# peripheral.net
KiCad netlist of a schematic drawn in Altium Designer
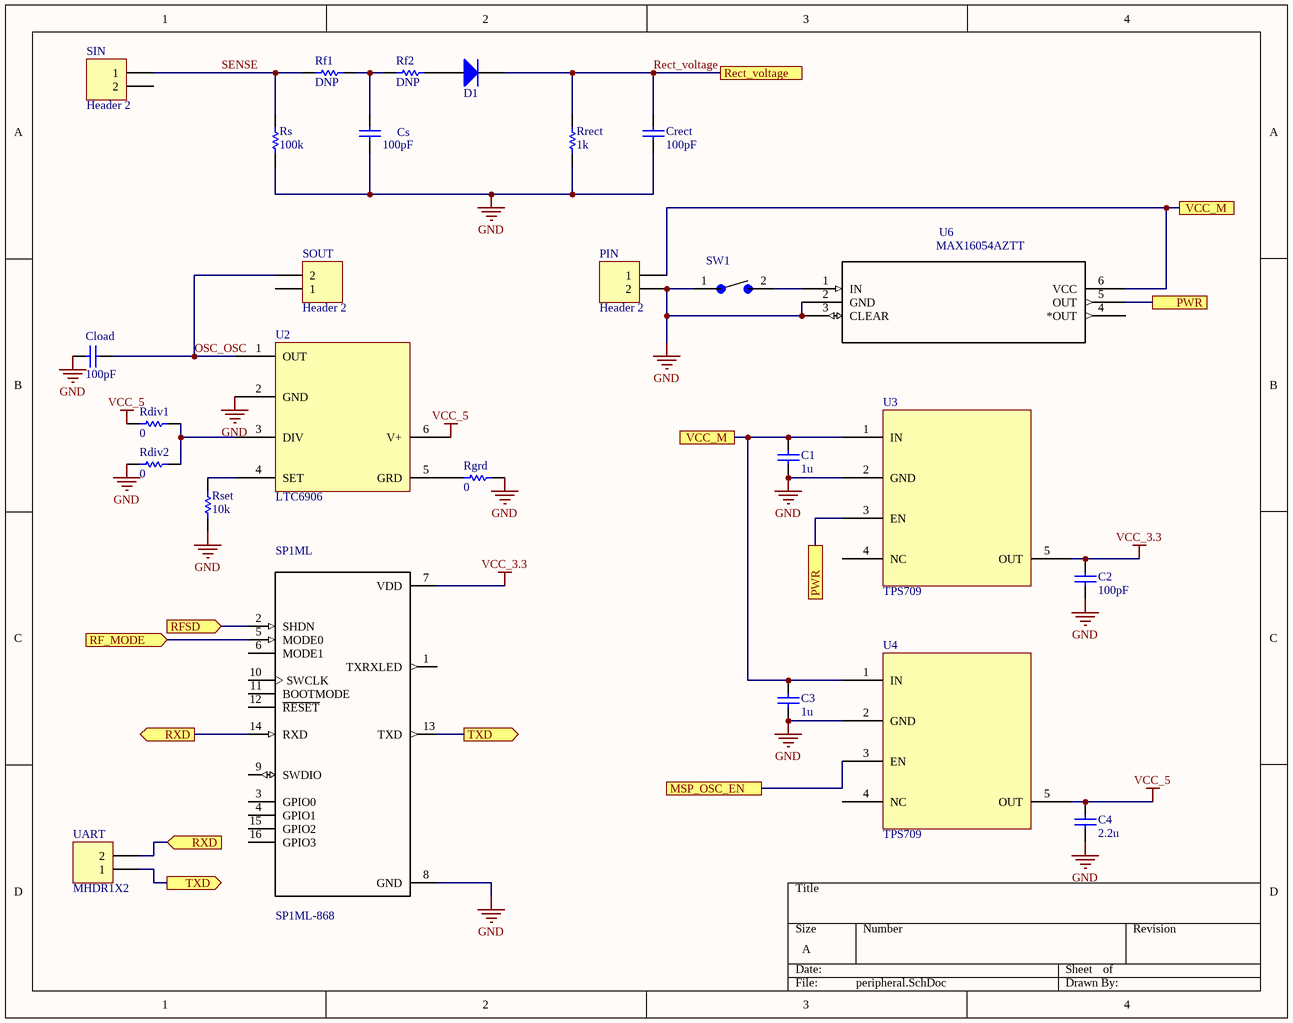
[diagram p0: peripheral.SchDoc]

(export (version "E")
  (design (tool "Eeschema 10.0.6"))
  (components
    (comp (ref "C1")
      (value "1u")
      (footprint "0402-W")
      (description "Ceramic Capacitor (Surface Mount)")
      (fields (field (name "MANUFACTURER") "Generic Ceramic Chip Cap (TBD)") (field (name "Comment") "Cap"))
      (libsource (lib "wisp") (part "Cap"))
    )
    (comp (ref "C2")
      (value "100pF")
      (footprint "0402-W")
      (description "Ceramic Capacitor (Surface Mount)")
      (fields (field (name "MANUFACTURER") "Generic Ceramic Chip Cap (TBD)") (field (name "Comment") "Cap"))
      (libsource (lib "wisp") (part "Cap"))
    )
    (comp (ref "C3")
      (value "1u")
      (footprint "0402-W")
      (description "Ceramic Capacitor (Surface Mount)")
      (fields (field (name "MANUFACTURER") "Generic Ceramic Chip Cap (TBD)") (field (name "Comment") "Cap"))
      (libsource (lib "wisp") (part "Cap"))
    )
    (comp (ref "C4")
      (value "2.2u")
      (footprint "0402-W")
      (description "Ceramic Capacitor (Surface Mount)")
      (fields (field (name "MANUFACTURER") "Generic Ceramic Chip Cap (TBD)") (field (name "Comment") "Cap"))
      (libsource (lib "wisp") (part "Cap"))
    )
    (comp (ref "Cload")
      (value "100pF")
      (footprint "0402-W")
      (description "Ceramic Capacitor (Surface Mount)")
      (fields (field (name "MANUFACTURER") "Generic Ceramic Chip Cap (TBD)") (field (name "Comment") "Cap"))
      (libsource (lib "wisp") (part "Cap"))
    )
    (comp (ref "Crect")
      (value "100pF")
      (footprint "0402-W")
      (description "Ceramic Capacitor (Surface Mount)")
      (fields (field (name "MANUFACTURER") "Generic Ceramic Chip Cap (TBD)") (field (name "Comment") "Cap"))
      (libsource (lib "wisp") (part "Cap"))
    )
    (comp (ref "Cs")
      (value "100pF")
      (footprint "0402-W")
      (description "Ceramic Capacitor (Surface Mount)")
      (fields (field (name "MANUFACTURER") "Generic Ceramic Chip Cap (TBD)") (field (name "Comment") "Cap"))
      (libsource (lib "wisp") (part "Cap"))
    )
    (comp (ref "D1")
      (value "Diode")
      (footprint "DIODE - SOD123")
      (description "General Purpose Diode")
      (libsource (lib "wisp") (part "Diode"))
    )
    (comp (ref "PIN")
      (value "Header 2")
      (footprint "HDR1X2")
      (description "Header, 2-Pin")
      (fields (field (name "PUBLISHER") "Altium Limited"))
      (libsource (lib "Miscellaneous Connectors") (part "Header 2"))
    )
    (comp (ref "Rdiv1")
      (value "0")
      (footprint "0402")
      (description "Chip Resistor (Surface Mount)")
      (fields (field (name "MANUFACTURER") "Generic Chip Res (TBD)") (field (name "Comment") "Res"))
      (libsource (lib "wisp") (part "Res"))
    )
    (comp (ref "Rdiv2")
      (value "0")
      (footprint "0402")
      (description "Chip Resistor (Surface Mount)")
      (fields (field (name "MANUFACTURER") "Generic Chip Res (TBD)") (field (name "Comment") "Res"))
      (libsource (lib "wisp") (part "Res"))
    )
    (comp (ref "Rf1")
      (value "DNP")
      (footprint "0402")
      (description "Chip Resistor (Surface Mount)")
      (fields (field (name "MANUFACTURER") "Generic Chip Res (TBD)") (field (name "Comment") "Res"))
      (libsource (lib "wisp") (part "Res"))
    )
    (comp (ref "Rf2")
      (value "DNP")
      (footprint "0402")
      (description "Chip Resistor (Surface Mount)")
      (fields (field (name "MANUFACTURER") "Generic Chip Res (TBD)") (field (name "Comment") "Res"))
      (libsource (lib "wisp") (part "Res"))
    )
    (comp (ref "Rgrd")
      (value "0")
      (footprint "0402")
      (description "Chip Resistor (Surface Mount)")
      (fields (field (name "MANUFACTURER") "Generic Chip Res (TBD)") (field (name "Comment") "Res"))
      (libsource (lib "wisp") (part "Res"))
    )
    (comp (ref "Rrect")
      (value "1k")
      (footprint "0402")
      (description "Chip Resistor (Surface Mount)")
      (fields (field (name "MANUFACTURER") "Generic Chip Res (TBD)") (field (name "Comment") "Res"))
      (libsource (lib "wisp") (part "Res"))
    )
    (comp (ref "Rs")
      (value "100k")
      (footprint "0402")
      (description "Chip Resistor (Surface Mount)")
      (fields (field (name "MANUFACTURER") "Generic Chip Res (TBD)") (field (name "Comment") "Res"))
      (libsource (lib "wisp") (part "Res"))
    )
    (comp (ref "Rset")
      (value "10k")
      (footprint "0402")
      (description "Chip Resistor (Surface Mount)")
      (fields (field (name "MANUFACTURER") "Generic Chip Res (TBD)") (field (name "Comment") "Res"))
      (libsource (lib "wisp") (part "Res"))
    )
    (comp (ref "SIN")
      (value "Header 2")
      (footprint "HDR1X2")
      (description "Header, 2-Pin")
      (fields (field (name "PUBLISHER") "Altium Limited"))
      (libsource (lib "Miscellaneous Connectors") (part "Header 2"))
    )
    (comp (ref "SOUT")
      (value "Header 2")
      (footprint "HDR1X2")
      (description "Header, 2-Pin")
      (fields (field (name "PUBLISHER") "Altium Limited"))
      (libsource (lib "") (part "Header 2_1"))
    )
    (comp (ref "SP1ML")
      (value "SP1ML-868")
      (footprint "STM_SP1ML-868")
      (description "RF TXRX MODULE ISM<1GHZ CHIP ANT")
      (fields (field (name "MF") "STMicroelectronics"))
      (libsource (lib "SP1ML-868") (part "SP1ML-868"))
    )
    (comp (ref "SW1")
      (value "FSMSM _1437566-3_")
      (footprint "TE_FSMSM")
      (description "FSMSM=3.5X6 SMT TACT")
      (fields (field (name "MF") "TE Connectivity") (field (name "MP") "FSMSM"))
      (libsource (lib "FSMSM") (part "FSMSM"))
    )
    (comp (ref "U2")
      (value "LTC6906")
      (footprint "6-Lead Plastic TSOT-23")
      (description "LP Oscilloter")
      (libsource (lib "Fromm") (part "LTC6906"))
    )
    (comp (ref "U3")
      (value "TPS709")
      (footprint "SOT95P280X145-5N")
      (description "Ultra low power Voltage Regulator")
      (libsource (lib "Fromm") (part "TPS709"))
    )
    (comp (ref "U4")
      (value "TPS709")
      (footprint "SOT95P280X145-5N")
      (description "Ultra low power Voltage Regulator")
      (libsource (lib "Fromm") (part "TPS709"))
    )
    (comp (ref "U6")
      (value "MAX16054AZTT")
      (footprint "21-0114C")
      (description "On/Off Controller With Debounce And +/-1")
      (fields (field (name "MF") "Maxim Integrated") (field (name "MP") "MAX16054AZT+"))
      (libsource (lib "MAX16054AZTT") (part "MAX16054AZTT"))
    )
    (comp (ref "UART")
      (value "MHDR1X2")
      (footprint "MHDR1X2")
      (description "Header, 2-Pin")
      (fields (field (name "PUBLISHER") "Altium Limited"))
      (libsource (lib "Miscellaneous Connectors") (part "MHDR1X2"))
    )
  )
  (nets
    (net (code "1") (name "/MSP_OSC_EN") (class "Default")
      (node (ref "U4") (pin "3") (pinfunction "EN_3") (pintype "passive"))
    )
    (net (code "2") (name "/OSC_OSC") (class "Default")
      (node (ref "Cload") (pin "2") (pinfunction "2_2") (pintype "passive"))
      (node (ref "SOUT") (pin "2") (pinfunction "2_2") (pintype "passive"))
      (node (ref "U2") (pin "1") (pinfunction "OUT_1") (pintype "passive"))
    )
    (net (code "3") (name "/PWR") (class "Default")
      (node (ref "U3") (pin "3") (pinfunction "EN_3") (pintype "passive"))
      (node (ref "U6") (pin "5") (pinfunction "OUT_5") (pintype "output"))
    )
    (net (code "4") (name "/RFSD") (class "Default")
      (node (ref "SP1ML") (pin "2") (pinfunction "SHDN_2") (pintype "input"))
    )
    (net (code "5") (name "/RF_MODE") (class "Default")
      (node (ref "SP1ML") (pin "5") (pinfunction "MODE0_5") (pintype "input"))
    )
    (net (code "6") (name "/RXD") (class "Default")
      (node (ref "SP1ML") (pin "14") (pinfunction "RXD_14") (pintype "input"))
      (node (ref "UART") (pin "2") (pinfunction "2_2") (pintype "passive"))
    )
    (net (code "7") (name "/Rect_voltage") (class "Default")
      (node (ref "Crect") (pin "2") (pinfunction "2_2") (pintype "passive"))
      (node (ref "D1") (pin "2") (pinfunction "C_2") (pintype "passive"))
      (node (ref "Rrect") (pin "2") (pinfunction "2_2") (pintype "passive"))
    )
    (net (code "8") (name "/SENSE") (class "Default")
      (node (ref "Rf1") (pin "1") (pinfunction "1_1") (pintype "passive"))
      (node (ref "Rs") (pin "2") (pinfunction "2_2") (pintype "passive"))
      (node (ref "SIN") (pin "1") (pinfunction "1_1") (pintype "passive"))
    )
    (net (code "9") (name "/TXD") (class "Default")
      (node (ref "SP1ML") (pin "13") (pinfunction "TXD_13") (pintype "output"))
      (node (ref "UART") (pin "1") (pinfunction "1_1") (pintype "passive"))
    )
    (net (code "10") (name "/VCC_M") (class "Default")
      (node (ref "C1") (pin "2") (pinfunction "2_2") (pintype "passive"))
      (node (ref "C3") (pin "2") (pinfunction "2_2") (pintype "passive"))
      (node (ref "PIN") (pin "1") (pinfunction "1_1") (pintype "passive"))
      (node (ref "U3") (pin "1") (pinfunction "IN_1") (pintype "passive"))
      (node (ref "U4") (pin "1") (pinfunction "IN_1") (pintype "passive"))
      (node (ref "U6") (pin "6") (pinfunction "VCC_6") (pintype "power_in"))
    )
    (net (code "11") (name "GND") (class "Default")
      (node (ref "C1") (pin "1") (pinfunction "1_1") (pintype "passive"))
      (node (ref "C2") (pin "1") (pinfunction "1_1") (pintype "passive"))
      (node (ref "C3") (pin "1") (pinfunction "1_1") (pintype "passive"))
      (node (ref "C4") (pin "1") (pinfunction "1_1") (pintype "passive"))
      (node (ref "Cload") (pin "1") (pinfunction "1_1") (pintype "passive"))
      (node (ref "Crect") (pin "1") (pinfunction "1_1") (pintype "passive"))
      (node (ref "Cs") (pin "1") (pinfunction "1_1") (pintype "passive"))
      (node (ref "PIN") (pin "2") (pinfunction "2_2") (pintype "passive"))
      (node (ref "Rdiv2") (pin "1") (pinfunction "1_1") (pintype "passive"))
      (node (ref "Rgrd") (pin "2") (pinfunction "2_2") (pintype "passive"))
      (node (ref "Rrect") (pin "1") (pinfunction "1_1") (pintype "passive"))
      (node (ref "Rs") (pin "1") (pinfunction "1_1") (pintype "passive"))
      (node (ref "Rset") (pin "1") (pinfunction "1_1") (pintype "passive"))
      (node (ref "SP1ML") (pin "8") (pinfunction "GND_8") (pintype "passive"))
      (node (ref "SW1") (pin "1") (pinfunction "1_1") (pintype "passive"))
      (node (ref "U2") (pin "2") (pinfunction "GND_2") (pintype "passive"))
      (node (ref "U3") (pin "2") (pinfunction "GND_2") (pintype "passive"))
      (node (ref "U4") (pin "2") (pinfunction "GND_2") (pintype "passive"))
      (node (ref "U6") (pin "2") (pinfunction "GND_2") (pintype "power_in"))
      (node (ref "U6") (pin "3") (pinfunction "CLEAR_3") (pintype "bidirectional"))
    )
    (net (code "12") (name "Net-(Cs-Pad2)") (class "Default")
      (node (ref "Cs") (pin "2") (pinfunction "2_2") (pintype "passive"))
      (node (ref "Rf1") (pin "2") (pinfunction "2_2") (pintype "passive"))
      (node (ref "Rf2") (pin "1") (pinfunction "1_1") (pintype "passive"))
    )
    (net (code "13") (name "Net-(D1-A)") (class "Default")
      (node (ref "D1") (pin "1") (pinfunction "A_1") (pintype "passive"))
      (node (ref "Rf2") (pin "2") (pinfunction "2_2") (pintype "passive"))
    )
    (net (code "14") (name "Net-(U2-DIV)") (class "Default")
      (node (ref "Rdiv1") (pin "2") (pinfunction "2_2") (pintype "passive"))
      (node (ref "Rdiv2") (pin "2") (pinfunction "2_2") (pintype "passive"))
      (node (ref "U2") (pin "3") (pinfunction "DIV_3") (pintype "passive"))
    )
    (net (code "15") (name "Net-(U2-GRD)") (class "Default")
      (node (ref "Rgrd") (pin "1") (pinfunction "1_1") (pintype "passive"))
      (node (ref "U2") (pin "5") (pinfunction "GRD_5") (pintype "passive"))
    )
    (net (code "16") (name "Net-(U2-SET)") (class "Default")
      (node (ref "Rset") (pin "2") (pinfunction "2_2") (pintype "passive"))
      (node (ref "U2") (pin "4") (pinfunction "SET_4") (pintype "passive"))
    )
    (net (code "17") (name "Net-(U6-IN)") (class "Default")
      (node (ref "SW1") (pin "2") (pinfunction "2_2") (pintype "passive"))
      (node (ref "U6") (pin "1") (pinfunction "IN_1") (pintype "input"))
    )
    (net (code "18") (name "VCC_3.3") (class "Default")
      (node (ref "C2") (pin "2") (pinfunction "2_2") (pintype "passive"))
      (node (ref "SP1ML") (pin "7") (pinfunction "VDD_7") (pintype "power_in"))
      (node (ref "U3") (pin "5") (pinfunction "OUT_5") (pintype "passive"))
    )
    (net (code "19") (name "VCC_5") (class "Default")
      (node (ref "C4") (pin "2") (pinfunction "2_2") (pintype "passive"))
      (node (ref "Rdiv1") (pin "1") (pinfunction "1_1") (pintype "passive"))
      (node (ref "U2") (pin "6") (pinfunction "V+_6") (pintype "passive"))
      (node (ref "U4") (pin "5") (pinfunction "OUT_5") (pintype "passive"))
    )
    (net (code "20") (name "unconnected-(SIN-Pad2)") (class "Default")
      (node (ref "SIN") (pin "2") (pinfunction "2_2") (pintype "passive"))
    )
    (net (code "21") (name "unconnected-(SOUT-Pad1)") (class "Default")
      (node (ref "SOUT") (pin "1") (pinfunction "1_1") (pintype "passive"))
    )
    (net (code "22") (name "unconnected-(SP1ML-BOOTMODE-Pad11)") (class "Default")
      (node (ref "SP1ML") (pin "11") (pinfunction "BOOTMODE_11") (pintype "passive"))
    )
    (net (code "23") (name "unconnected-(SP1ML-GPIO0-Pad3)") (class "Default")
      (node (ref "SP1ML") (pin "3") (pinfunction "GPIO0_3") (pintype "passive"))
    )
    (net (code "24") (name "unconnected-(SP1ML-GPIO1-Pad4)") (class "Default")
      (node (ref "SP1ML") (pin "4") (pinfunction "GPIO1_4") (pintype "passive"))
    )
    (net (code "25") (name "unconnected-(SP1ML-GPIO2-Pad15)") (class "Default")
      (node (ref "SP1ML") (pin "15") (pinfunction "GPIO2_15") (pintype "passive"))
    )
    (net (code "26") (name "unconnected-(SP1ML-GPIO3-Pad16)") (class "Default")
      (node (ref "SP1ML") (pin "16") (pinfunction "GPIO3_16") (pintype "passive"))
    )
    (net (code "27") (name "unconnected-(SP1ML-MODE1-Pad6)") (class "Default")
      (node (ref "SP1ML") (pin "6") (pinfunction "MODE1_6") (pintype "passive"))
    )
    (net (code "28") (name "unconnected-(SP1ML-SWCLK-Pad10)") (class "Default")
      (node (ref "SP1ML") (pin "10") (pinfunction "SWCLK_10") (pintype "passive"))
    )
    (net (code "29") (name "unconnected-(SP1ML-SWDIO-Pad9)") (class "Default")
      (node (ref "SP1ML") (pin "9") (pinfunction "SWDIO_9") (pintype "bidirectional"))
    )
    (net (code "30") (name "unconnected-(SP1ML-TXRXLED-Pad1)") (class "Default")
      (node (ref "SP1ML") (pin "1") (pinfunction "TXRXLED_1") (pintype "output"))
    )
    (net (code "31") (name "unconnected-(SP1ML-~{RESET}-Pad12)") (class "Default")
      (node (ref "SP1ML") (pin "12") (pinfunction "~{RESET}_12") (pintype "passive"))
    )
    (net (code "32") (name "unconnected-(U3-NC-Pad4)") (class "Default")
      (node (ref "U3") (pin "4") (pinfunction "NC_4") (pintype "passive"))
    )
    (net (code "33") (name "unconnected-(U4-NC-Pad4)") (class "Default")
      (node (ref "U4") (pin "4") (pinfunction "NC_4") (pintype "passive"))
    )
    (net (code "34") (name "unconnected-(U6-*OUT-Pad4)") (class "Default")
      (node (ref "U6") (pin "4") (pinfunction "*OUT_4") (pintype "output"))
    )
  )
)
